# Real_Steel_Robotics.net
KiCad netlist of a schematic drawn in Altium Designer
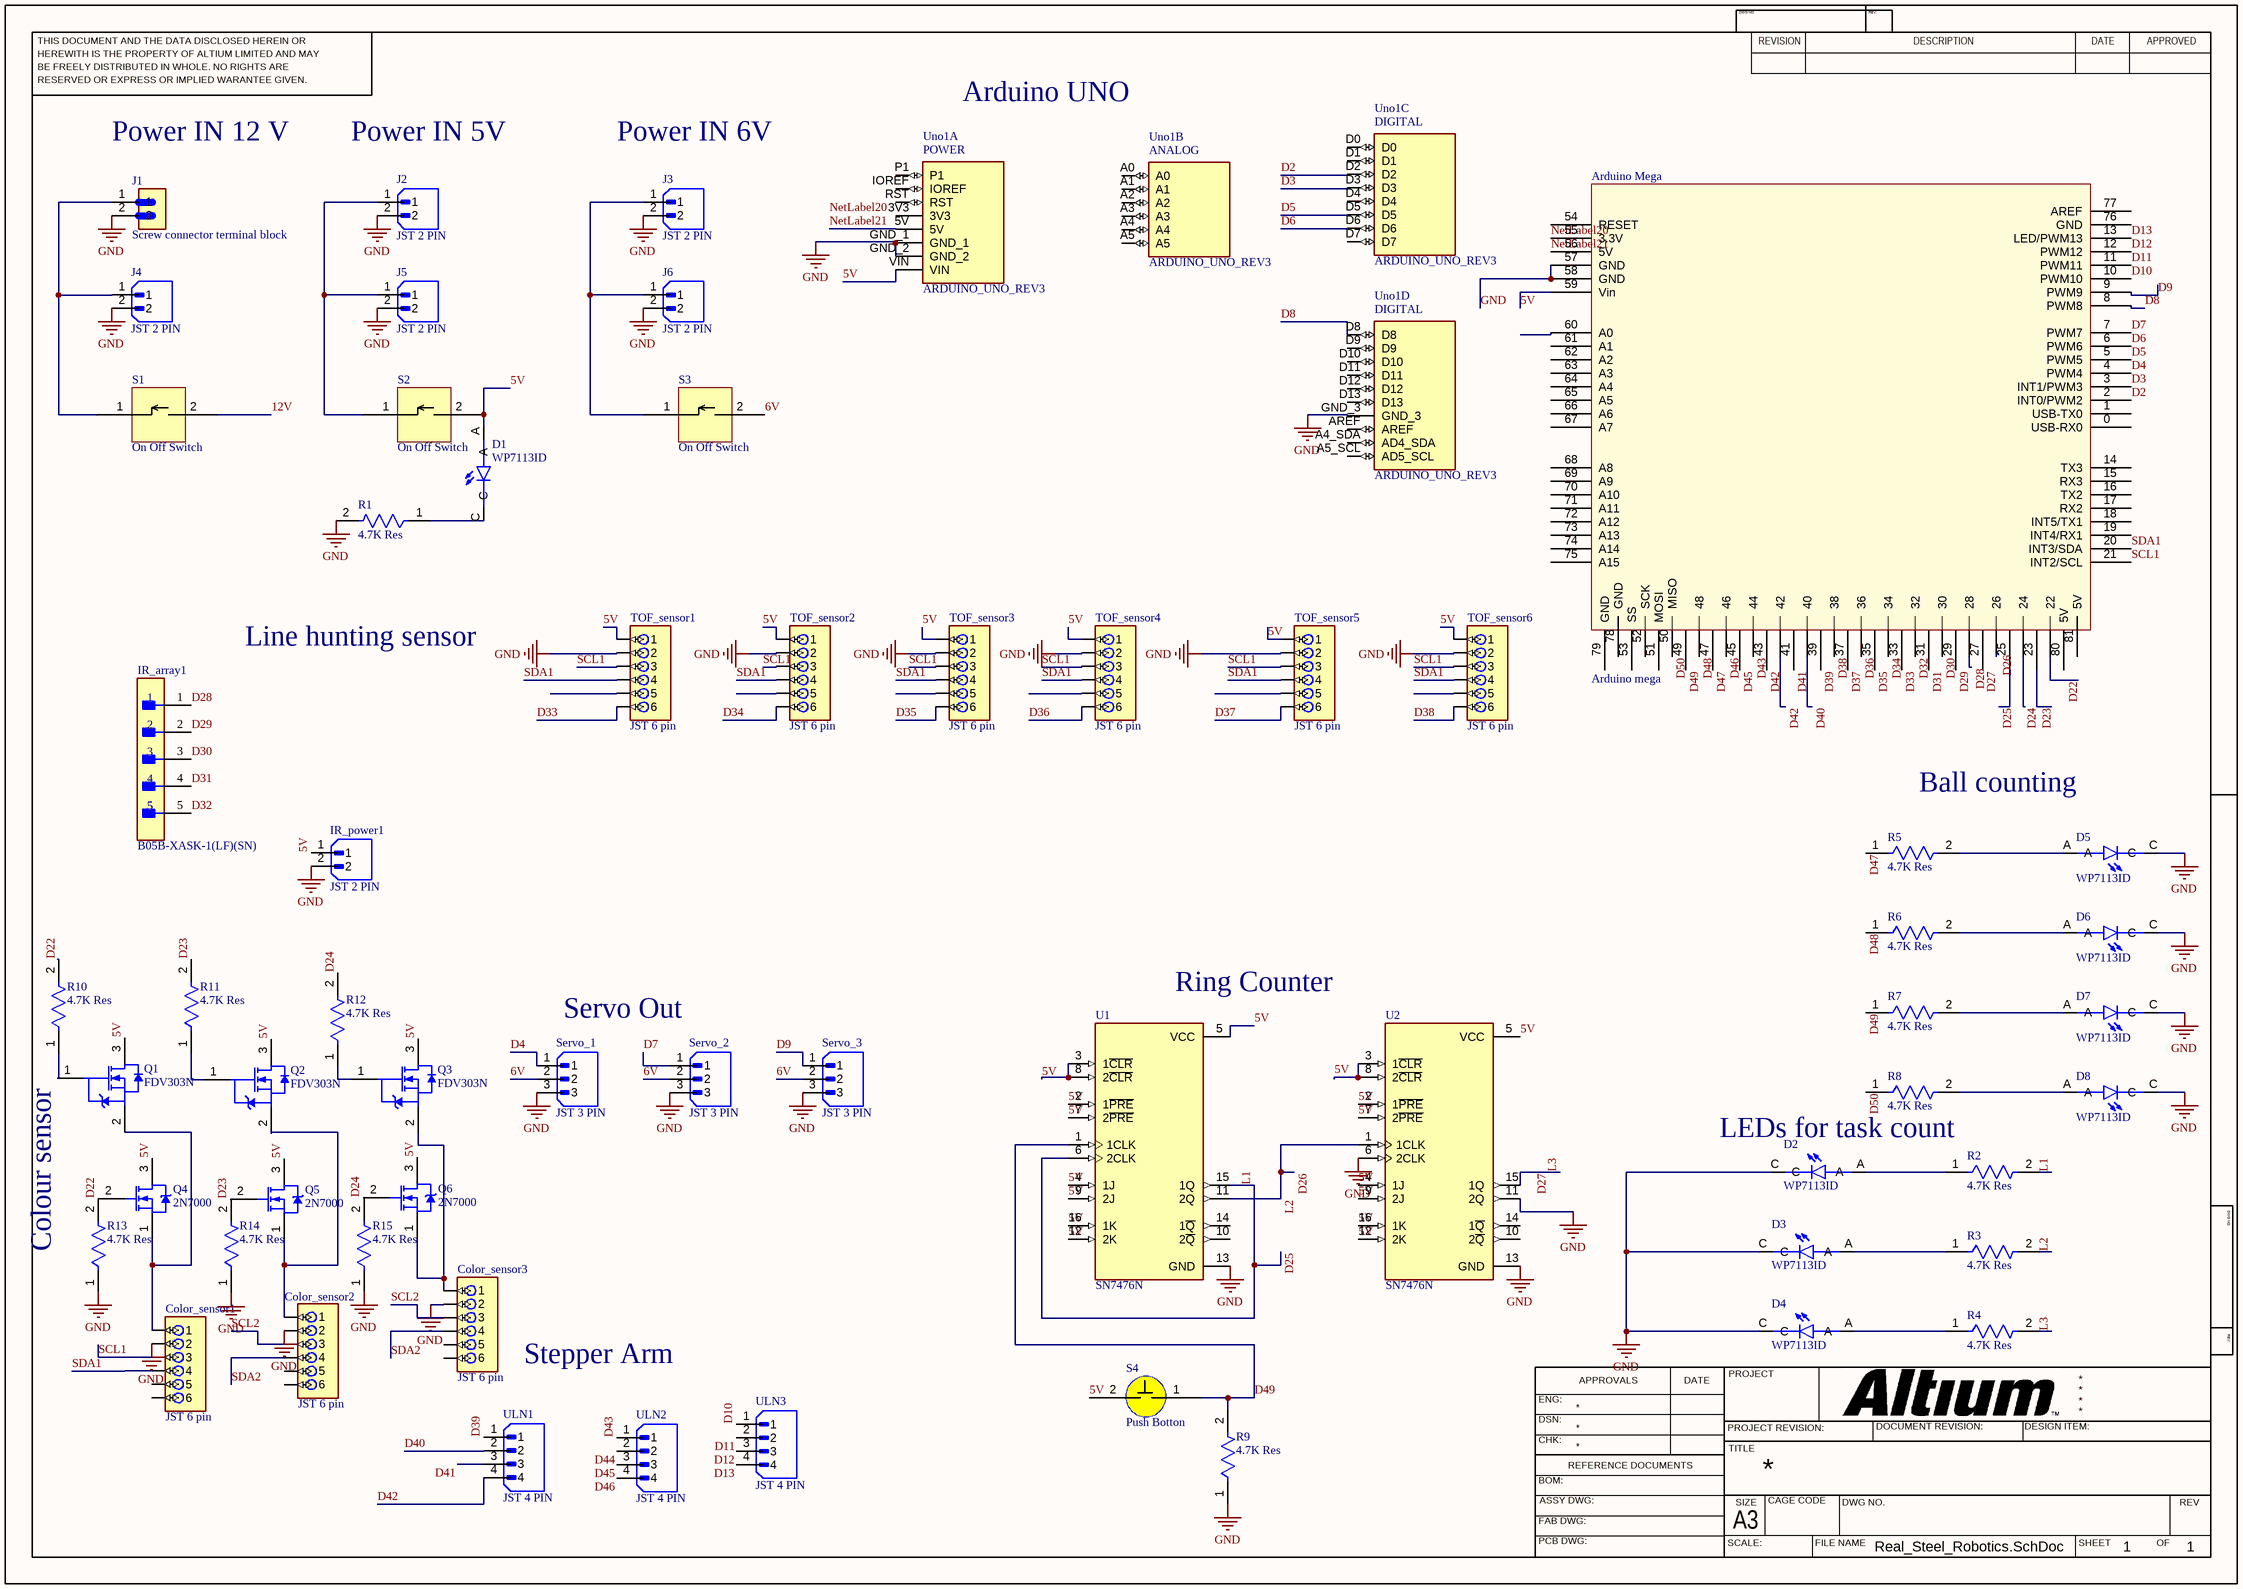
[diagram p0:  Real_Steel_Robotics.SchDoc]

(export (version "E")
  (design (tool "Eeschema 10.0.6"))
  (components
    (comp (ref "Arduino Mega")
      (value "Arduino mega")
      (footprint "Arduino mega")
      (libsource (lib "Real_Steel_Robotics") (part "Arduino mega"))
    )
    (comp (ref "Color_sensor1")
      (value "JST 6 pin")
      (footprint "JST 6 PIN")
      (description "Header B6B-ZR, 1.50mm, 6-contacts, top entry, THT, /2000/box")
      (fields (field (name "MANUFACTURER") "JST") (field (name "MANUFACTURER PART NUMBER") "B6B-ZR"))
      (libsource (lib "Real_Steel_Robotics") (part "JST 6 pin"))
    )
    (comp (ref "Color_sensor2")
      (value "JST 6 pin")
      (footprint "JST 6 PIN")
      (description "Header B6B-ZR, 1.50mm, 6-contacts, top entry, THT, /2000/box")
      (fields (field (name "MANUFACTURER") "JST") (field (name "MANUFACTURER PART NUMBER") "B6B-ZR"))
      (libsource (lib "Real_Steel_Robotics") (part "JST 6 pin"))
    )
    (comp (ref "Color_sensor3")
      (value "JST 6 pin")
      (footprint "JST 6 PIN")
      (description "Header B6B-ZR, 1.50mm, 6-contacts, top entry, THT, /2000/box")
      (fields (field (name "MANUFACTURER") "JST") (field (name "MANUFACTURER PART NUMBER") "B6B-ZR"))
      (libsource (lib "Real_Steel_Robotics") (part "JST 6 pin"))
    )
    (comp (ref "D1")
      (value "WP7113ID")
      (footprint "LED_WP7113ID")
      (description "Red 617nm LED Indication - Discrete 2V Radial")
      (fields (field (name "MF") "Kingbright"))
      (libsource (lib "Real_Steel_Robotics") (part "WP7113ID"))
    )
    (comp (ref "D2")
      (value "WP7113ID")
      (footprint "LED_WP7113ID")
      (description "Red 617nm LED Indication - Discrete 2V Radial")
      (fields (field (name "MF") "Kingbright"))
      (libsource (lib "Real_Steel_Robotics") (part "WP7113ID"))
    )
    (comp (ref "D3")
      (value "WP7113ID")
      (footprint "LED_WP7113ID")
      (description "Red 617nm LED Indication - Discrete 2V Radial")
      (fields (field (name "MF") "Kingbright"))
      (libsource (lib "Real_Steel_Robotics") (part "WP7113ID"))
    )
    (comp (ref "D4")
      (value "WP7113ID")
      (footprint "LED_WP7113ID")
      (description "Red 617nm LED Indication - Discrete 2V Radial")
      (fields (field (name "MF") "Kingbright"))
      (libsource (lib "Real_Steel_Robotics") (part "WP7113ID"))
    )
    (comp (ref "D5")
      (value "WP7113ID")
      (footprint "LED_WP7113ID")
      (description "Red 617nm LED Indication - Discrete 2V Radial")
      (fields (field (name "MF") "Kingbright"))
      (libsource (lib "Real_Steel_Robotics") (part "WP7113ID"))
    )
    (comp (ref "D6")
      (value "WP7113ID")
      (footprint "LED_WP7113ID")
      (description "Red 617nm LED Indication - Discrete 2V Radial")
      (fields (field (name "MF") "Kingbright"))
      (libsource (lib "Real_Steel_Robotics") (part "WP7113ID"))
    )
    (comp (ref "D7")
      (value "WP7113ID")
      (footprint "LED_WP7113ID")
      (description "Red 617nm LED Indication - Discrete 2V Radial")
      (fields (field (name "MF") "Kingbright"))
      (libsource (lib "Real_Steel_Robotics") (part "WP7113ID"))
    )
    (comp (ref "D8")
      (value "WP7113ID")
      (footprint "LED_WP7113ID")
      (description "Red 617nm LED Indication - Discrete 2V Radial")
      (fields (field (name "MF") "Kingbright"))
      (libsource (lib "Real_Steel_Robotics") (part "WP7113ID"))
    )
    (comp (ref "IR_array1")
      (value "B05B-XASK-1(LF)(SN)")
      (footprint "JST 5 PIN")
      (description "CONN HEADER VERT 5POS 2.5MM")
      (libsource (lib "Real_Steel_Robotics") (part "JST 5 PIN"))
    )
    (comp (ref "IR_power1")
      (value "JST 2 PIN")
      (footprint "JST 2 PIN")
      (description "Connector Header Through Hole 2 position 0.098 (2.50mm)")
      (fields (field (name "MF") "JST Sales") (field (name "MP") "B2B-XH-A (LF)(SN)"))
      (libsource (lib "Real_Steel_Robotics") (part "JST 2 PIN"))
    )
    (comp (ref "J1")
      (value "Screw connector terminal block")
      (footprint "Screw Connector")
      (libsource (lib "Real_Steel_Robotics") (part "Screw connector terminal block"))
    )
    (comp (ref "J2")
      (value "JST 2 PIN")
      (footprint "JST 2 PIN")
      (description "Connector Header Through Hole 2 position 0.098 (2.50mm)")
      (fields (field (name "MF") "JST Sales") (field (name "MP") "B2B-XH-A (LF)(SN)"))
      (libsource (lib "Real_Steel_Robotics") (part "JST 2 PIN"))
    )
    (comp (ref "J3")
      (value "JST 2 PIN")
      (footprint "JST 2 PIN")
      (description "Connector Header Through Hole 2 position 0.098 (2.50mm)")
      (fields (field (name "MF") "JST Sales") (field (name "MP") "B2B-XH-A (LF)(SN)"))
      (libsource (lib "Real_Steel_Robotics") (part "JST 2 PIN"))
    )
    (comp (ref "J4")
      (value "JST 2 PIN")
      (footprint "JST 2 PIN")
      (description "Connector Header Through Hole 2 position 0.098 (2.50mm)")
      (fields (field (name "MF") "JST Sales") (field (name "MP") "B2B-XH-A (LF)(SN)"))
      (libsource (lib "Real_Steel_Robotics") (part "JST 2 PIN"))
    )
    (comp (ref "J5")
      (value "JST 2 PIN")
      (footprint "JST 2 PIN")
      (description "Connector Header Through Hole 2 position 0.098 (2.50mm)")
      (fields (field (name "MF") "JST Sales") (field (name "MP") "B2B-XH-A (LF)(SN)"))
      (libsource (lib "Real_Steel_Robotics") (part "JST 2 PIN"))
    )
    (comp (ref "J6")
      (value "JST 2 PIN")
      (footprint "JST 2 PIN")
      (description "Connector Header Through Hole 2 position 0.098 (2.50mm)")
      (fields (field (name "MF") "JST Sales") (field (name "MP") "B2B-XH-A (LF)(SN)"))
      (libsource (lib "Real_Steel_Robotics") (part "JST 2 PIN"))
    )
    (comp (ref "Q1")
      (value "FDV303N")
      (footprint "FAIR-FDV303N-3_V")
      (fields (field (name "MANUFACTURER") "Fairchild"))
      (libsource (lib "Altium Content Vault") (part "NEMOS-GSD-3_D"))
    )
    (comp (ref "Q2")
      (value "FDV303N")
      (footprint "FAIR-FDV303N-3_V")
      (fields (field (name "MANUFACTURER") "Fairchild"))
      (libsource (lib "Altium Content Vault") (part "NEMOS-GSD-3_D"))
    )
    (comp (ref "Q3")
      (value "FDV303N")
      (footprint "FAIR-FDV303N-3_V")
      (fields (field (name "MANUFACTURER") "Fairchild"))
      (libsource (lib "Altium Content Vault") (part "NEMOS-GSD-3_D"))
    )
    (comp (ref "Q4")
      (value "2N7000")
      (footprint "ONSC-TO-92-3-29-11")
      (description "Small Signal MOSFET, 200 mA, 60 V, N-Channel, 3-Pin TO-92, Bulk Box")
      (fields (field (name "MANUFACTURER") "On Semiconductor"))
      (libsource (lib "Altium Content Vault") (part "ONSC-NMOS-S1G2D3-3"))
    )
    (comp (ref "Q5")
      (value "2N7000")
      (footprint "ONSC-TO-92-3-29-11")
      (description "Small Signal MOSFET, 200 mA, 60 V, N-Channel, 3-Pin TO-92, Bulk Box")
      (fields (field (name "MANUFACTURER") "On Semiconductor"))
      (libsource (lib "Altium Content Vault") (part "ONSC-NMOS-S1G2D3-3"))
    )
    (comp (ref "Q6")
      (value "2N7000")
      (footprint "ONSC-TO-92-3-29-11")
      (description "Small Signal MOSFET, 200 mA, 60 V, N-Channel, 3-Pin TO-92, Bulk Box")
      (fields (field (name "MANUFACTURER") "On Semiconductor"))
      (libsource (lib "Altium Content Vault") (part "ONSC-NMOS-S1G2D3-3"))
    )
    (comp (ref "R1")
      (value "4.7K Res")
      (footprint "4.7K res")
      (libsource (lib "Real_Steel_Robotics") (part "4.7K Res"))
    )
    (comp (ref "R2")
      (value "4.7K Res")
      (footprint "4.7K res")
      (libsource (lib "Real_Steel_Robotics") (part "4.7K Res"))
    )
    (comp (ref "R3")
      (value "4.7K Res")
      (footprint "4.7K res")
      (libsource (lib "Real_Steel_Robotics") (part "4.7K Res"))
    )
    (comp (ref "R4")
      (value "4.7K Res")
      (footprint "4.7K res")
      (libsource (lib "Real_Steel_Robotics") (part "4.7K Res"))
    )
    (comp (ref "R5")
      (value "4.7K Res")
      (footprint "4.7K res")
      (libsource (lib "Real_Steel_Robotics") (part "4.7K Res"))
    )
    (comp (ref "R6")
      (value "4.7K Res")
      (footprint "4.7K res")
      (libsource (lib "Real_Steel_Robotics") (part "4.7K Res"))
    )
    (comp (ref "R7")
      (value "4.7K Res")
      (footprint "4.7K res")
      (libsource (lib "Real_Steel_Robotics") (part "4.7K Res"))
    )
    (comp (ref "R8")
      (value "4.7K Res")
      (footprint "4.7K res")
      (libsource (lib "Real_Steel_Robotics") (part "4.7K Res"))
    )
    (comp (ref "R9")
      (value "4.7K Res")
      (footprint "4.7K res")
      (libsource (lib "Real_Steel_Robotics") (part "4.7K Res"))
    )
    (comp (ref "R10")
      (value "4.7K Res")
      (footprint "4.7K res")
      (libsource (lib "Real_Steel_Robotics") (part "4.7K Res"))
    )
    (comp (ref "R11")
      (value "4.7K Res")
      (footprint "4.7K res")
      (libsource (lib "Real_Steel_Robotics") (part "4.7K Res"))
    )
    (comp (ref "R12")
      (value "4.7K Res")
      (footprint "4.7K res")
      (libsource (lib "Real_Steel_Robotics") (part "4.7K Res"))
    )
    (comp (ref "R13")
      (value "4.7K Res")
      (footprint "4.7K res")
      (libsource (lib "Real_Steel_Robotics") (part "4.7K Res"))
    )
    (comp (ref "R14")
      (value "4.7K Res")
      (footprint "4.7K res")
      (libsource (lib "Real_Steel_Robotics") (part "4.7K Res"))
    )
    (comp (ref "R15")
      (value "4.7K Res")
      (footprint "4.7K res")
      (libsource (lib "Real_Steel_Robotics") (part "4.7K Res"))
    )
    (comp (ref "S1")
      (value "On Off Switch")
      (footprint "Switch")
      (libsource (lib "Real_Steel_Robotics") (part "On Off Switch"))
    )
    (comp (ref "S2")
      (value "On Off Switch")
      (footprint "Switch")
      (libsource (lib "Real_Steel_Robotics") (part "On Off Switch"))
    )
    (comp (ref "S3")
      (value "On Off Switch")
      (footprint "Switch")
      (libsource (lib "Real_Steel_Robotics") (part "On Off Switch"))
    )
    (comp (ref "S4")
      (value "Push Botton")
      (footprint "Push botton")
      (libsource (lib "Real_Steel_Robotics") (part "Push Botton"))
    )
    (comp (ref "Servo_1")
      (value "JST 3 PIN")
      (footprint "JST 3 PIN")
      (libsource (lib "Real_Steel_Robotics") (part "JST 3 PIN"))
    )
    (comp (ref "Servo_2")
      (value "JST 3 PIN")
      (footprint "JST 3 PIN")
      (libsource (lib "Real_Steel_Robotics") (part "JST 3 PIN"))
    )
    (comp (ref "Servo_3")
      (value "JST 3 PIN")
      (footprint "JST 3 PIN")
      (libsource (lib "Real_Steel_Robotics") (part "JST 3 PIN"))
    )
    (comp (ref "TOF_sensor1")
      (value "JST 6 pin")
      (footprint "JST 6 PIN")
      (description "Header B6B-ZR, 1.50mm, 6-contacts, top entry, THT, /2000/box")
      (fields (field (name "MANUFACTURER") "JST") (field (name "MANUFACTURER PART NUMBER") "B6B-ZR"))
      (libsource (lib "Real_Steel_Robotics") (part "JST 6 pin"))
    )
    (comp (ref "TOF_sensor2")
      (value "JST 6 pin")
      (footprint "JST 6 PIN")
      (description "Header B6B-ZR, 1.50mm, 6-contacts, top entry, THT, /2000/box")
      (fields (field (name "MANUFACTURER") "JST") (field (name "MANUFACTURER PART NUMBER") "B6B-ZR"))
      (libsource (lib "Real_Steel_Robotics") (part "JST 6 pin"))
    )
    (comp (ref "TOF_sensor3")
      (value "JST 6 pin")
      (footprint "JST 6 PIN")
      (description "Header B6B-ZR, 1.50mm, 6-contacts, top entry, THT, /2000/box")
      (fields (field (name "MANUFACTURER") "JST") (field (name "MANUFACTURER PART NUMBER") "B6B-ZR"))
      (libsource (lib "Real_Steel_Robotics") (part "JST 6 pin"))
    )
    (comp (ref "TOF_sensor4")
      (value "JST 6 pin")
      (footprint "JST 6 PIN")
      (description "Header B6B-ZR, 1.50mm, 6-contacts, top entry, THT, /2000/box")
      (fields (field (name "MANUFACTURER") "JST") (field (name "MANUFACTURER PART NUMBER") "B6B-ZR"))
      (libsource (lib "Real_Steel_Robotics") (part "JST 6 pin"))
    )
    (comp (ref "TOF_sensor5")
      (value "JST 6 pin")
      (footprint "JST 6 PIN")
      (description "Header B6B-ZR, 1.50mm, 6-contacts, top entry, THT, /2000/box")
      (fields (field (name "MANUFACTURER") "JST") (field (name "MANUFACTURER PART NUMBER") "B6B-ZR"))
      (libsource (lib "Real_Steel_Robotics") (part "JST 6 pin"))
    )
    (comp (ref "TOF_sensor6")
      (value "JST 6 pin")
      (footprint "JST 6 PIN")
      (description "Header B6B-ZR, 1.50mm, 6-contacts, top entry, THT, /2000/box")
      (fields (field (name "MANUFACTURER") "JST") (field (name "MANUFACTURER PART NUMBER") "B6B-ZR"))
      (libsource (lib "Real_Steel_Robotics") (part "JST 6 pin"))
    )
    (comp (ref "U1")
      (value "SN7476N")
      (footprint "SN7476 IC")
      (description "Flip Flops Dual J-K Positive-Edge-Triggered Flip-Flops with Preset and Clear 16-PDIP 0 to 70")
      (fields (field (name "MF") "Texas Instruments"))
      (libsource (lib "Real_Steel_Robotics") (part "SN7476N"))
    )
    (comp (ref "U2")
      (value "SN7476N")
      (footprint "SN7476 IC")
      (description "Flip Flops Dual J-K Positive-Edge-Triggered Flip-Flops with Preset and Clear 16-PDIP 0 to 70")
      (fields (field (name "MF") "Texas Instruments"))
      (libsource (lib "Real_Steel_Robotics") (part "SN7476N"))
    )
    (comp (ref "ULN1")
      (value "JST 4 PIN")
      (footprint "JST 4 PIN")
      (libsource (lib "Real_Steel_Robotics") (part "JST 4 PIN"))
    )
    (comp (ref "ULN2")
      (value "JST 4 PIN")
      (footprint "JST 4 PIN")
      (libsource (lib "Real_Steel_Robotics") (part "JST 4 PIN"))
    )
    (comp (ref "ULN3")
      (value "JST 4 PIN")
      (footprint "JST 4 PIN")
      (libsource (lib "Real_Steel_Robotics") (part "JST 4 PIN"))
    )
    (comp (ref "Uno1")
      (value "ARDUINO_UNO_REV3")
      (footprint "ARDUINO_ARDUINO_UNO_REV3")
      (description "Microcontroller board based on the ATmega328P.")
      (fields (field (name "MF") "Arduino") (field (name "MP") "ARDUINO UNO REV3"))
      (libsource (lib "Real_Steel_Robotics") (part "ARDUINO_UNO_REV3"))
    )
  )
  (nets
    (net (code "1") (name "/5V") (class "Default")
      (node (ref "Arduino Mega") (pin "59") (pinfunction "Vin_59") (pintype "passive"))
      (node (ref "D1") (pin "A") (pinfunction "A_A") (pintype "passive"))
      (node (ref "IR_power1") (pin "1") (pinfunction "1_1") (pintype "passive"))
      (node (ref "Q1") (pin "3") (pinfunction "D_3") (pintype "passive"))
      (node (ref "Q2") (pin "3") (pinfunction "D_3") (pintype "passive"))
      (node (ref "Q3") (pin "3") (pinfunction "D_3") (pintype "passive"))
      (node (ref "Q4") (pin "3") (pinfunction "D_3") (pintype "passive"))
      (node (ref "Q5") (pin "3") (pinfunction "D_3") (pintype "passive"))
      (node (ref "Q6") (pin "3") (pinfunction "D_3") (pintype "passive"))
      (node (ref "S2") (pin "2") (pintype "passive"))
      (node (ref "S4") (pin "2") (pinfunction "P29_2") (pintype "passive"))
      (node (ref "TOF_sensor1") (pin "1") (pinfunction "1_1") (pintype "bidirectional"))
      (node (ref "TOF_sensor2") (pin "1") (pinfunction "1_1") (pintype "bidirectional"))
      (node (ref "TOF_sensor3") (pin "1") (pinfunction "1_1") (pintype "bidirectional"))
      (node (ref "TOF_sensor4") (pin "1") (pinfunction "1_1") (pintype "bidirectional"))
      (node (ref "TOF_sensor5") (pin "1") (pinfunction "1_1") (pintype "bidirectional"))
      (node (ref "TOF_sensor6") (pin "1") (pinfunction "1_1") (pintype "bidirectional"))
      (node (ref "U1") (pin "12") (pinfunction "2K_12") (pintype "input"))
      (node (ref "U1") (pin "16") (pinfunction "1K_16") (pintype "input"))
      (node (ref "U1") (pin "2") (pinfunction "1~{PRE}_2") (pintype "input"))
      (node (ref "U1") (pin "3") (pinfunction "1~{CLR}_3") (pintype "input"))
      (node (ref "U1") (pin "4") (pinfunction "1J_4") (pintype "input"))
      (node (ref "U1") (pin "5") (pinfunction "VCC_5") (pintype "power_in"))
      (node (ref "U1") (pin "7") (pinfunction "2~{PRE}_7") (pintype "input"))
      (node (ref "U1") (pin "8") (pinfunction "2~{CLR}_8") (pintype "input"))
      (node (ref "U1") (pin "9") (pinfunction "2J_9") (pintype "input"))
      (node (ref "U2") (pin "12") (pinfunction "2K_12") (pintype "input"))
      (node (ref "U2") (pin "16") (pinfunction "1K_16") (pintype "input"))
      (node (ref "U2") (pin "2") (pinfunction "1~{PRE}_2") (pintype "input"))
      (node (ref "U2") (pin "3") (pinfunction "1~{CLR}_3") (pintype "input"))
      (node (ref "U2") (pin "4") (pinfunction "1J_4") (pintype "input"))
      (node (ref "U2") (pin "5") (pinfunction "VCC_5") (pintype "power_in"))
      (node (ref "U2") (pin "7") (pinfunction "2~{PRE}_7") (pintype "input"))
      (node (ref "U2") (pin "8") (pinfunction "2~{CLR}_8") (pintype "input"))
      (node (ref "U2") (pin "9") (pinfunction "2J_9") (pintype "input"))
      (node (ref "Uno1") (pin "VIN") (pinfunction "VIN_VIN") (pintype "power_in"))
    )
    (net (code "2") (name "/6V") (class "Default")
      (node (ref "S3") (pin "2") (pintype "passive"))
      (node (ref "Servo_1") (pin "2") (pinfunction "2_2") (pintype "passive"))
      (node (ref "Servo_2") (pin "2") (pinfunction "2_2") (pintype "passive"))
      (node (ref "Servo_3") (pin "2") (pinfunction "2_2") (pintype "passive"))
    )
    (net (code "3") (name "/12V") (class "Default") (node (ref "S1") (pin "2") (pintype "passive")))
    (net (code "4") (name "/D2") (class "Default")
      (node (ref "Arduino Mega") (pin "2") (pinfunction "INT0/PWM2_2") (pintype "passive"))
      (node (ref "Uno1") (pin "D2") (pinfunction "D2_D2") (pintype "bidirectional"))
    )
    (net (code "5") (name "/D3") (class "Default")
      (node (ref "Arduino Mega") (pin "3") (pinfunction "INT1/PWM3_3") (pintype "passive"))
      (node (ref "Uno1") (pin "D3") (pinfunction "D3_D3") (pintype "bidirectional"))
    )
    (net (code "6") (name "/D4") (class "Default")
      (node (ref "Arduino Mega") (pin "4") (pinfunction "PWM4_4") (pintype "passive"))
      (node (ref "Servo_1") (pin "1") (pinfunction "1_1") (pintype "passive"))
    )
    (net (code "7") (name "/D5") (class "Default")
      (node (ref "Arduino Mega") (pin "5") (pinfunction "PWM5_5") (pintype "passive"))
      (node (ref "Uno1") (pin "D5") (pinfunction "D5_D5") (pintype "bidirectional"))
    )
    (net (code "8") (name "/D6") (class "Default")
      (node (ref "Arduino Mega") (pin "6") (pinfunction "PWM6_6") (pintype "passive"))
      (node (ref "Uno1") (pin "D6") (pinfunction "D6_D6") (pintype "bidirectional"))
    )
    (net (code "9") (name "/D7") (class "Default")
      (node (ref "Arduino Mega") (pin "7") (pinfunction "PWM7_7") (pintype "passive"))
      (node (ref "Servo_2") (pin "1") (pinfunction "1_1") (pintype "passive"))
    )
    (net (code "10") (name "/D8") (class "Default")
      (node (ref "Arduino Mega") (pin "8") (pinfunction "PWM8_8") (pintype "passive"))
      (node (ref "Uno1") (pin "D8") (pinfunction "D8_D8") (pintype "bidirectional"))
    )
    (net (code "11") (name "/D9") (class "Default")
      (node (ref "Arduino Mega") (pin "9") (pinfunction "PWM9_9") (pintype "passive"))
      (node (ref "Servo_3") (pin "1") (pinfunction "1_1") (pintype "passive"))
    )
    (net (code "12") (name "/D10") (class "Default")
      (node (ref "Arduino Mega") (pin "10") (pinfunction "PWM10_10") (pintype "passive"))
      (node (ref "ULN3") (pin "1") (pinfunction "1_1") (pintype "passive"))
    )
    (net (code "13") (name "/D11") (class "Default")
      (node (ref "Arduino Mega") (pin "11") (pinfunction "PWM11_11") (pintype "passive"))
      (node (ref "ULN3") (pin "2") (pinfunction "2_2") (pintype "passive"))
    )
    (net (code "14") (name "/D12") (class "Default")
      (node (ref "Arduino Mega") (pin "12") (pinfunction "PWM12_12") (pintype "passive"))
      (node (ref "ULN3") (pin "3") (pinfunction "3_3") (pintype "passive"))
    )
    (net (code "15") (name "/D13") (class "Default")
      (node (ref "Arduino Mega") (pin "13") (pinfunction "LED/PWM13_13") (pintype "passive"))
      (node (ref "ULN3") (pin "4") (pinfunction "4_4") (pintype "passive"))
    )
    (net (code "16") (name "/D22") (class "Default")
      (node (ref "Arduino Mega") (pin "22") (pinfunction "22_22") (pintype "passive"))
      (node (ref "Q4") (pin "2") (pinfunction "G_2") (pintype "passive"))
      (node (ref "R10") (pin "2") (pinfunction "2_2") (pintype "passive"))
      (node (ref "R13") (pin "2") (pinfunction "2_2") (pintype "passive"))
    )
    (net (code "17") (name "/D23") (class "Default")
      (node (ref "Arduino Mega") (pin "23") (pinfunction "23_23") (pintype "passive"))
      (node (ref "Q5") (pin "2") (pinfunction "G_2") (pintype "passive"))
      (node (ref "R11") (pin "2") (pinfunction "2_2") (pintype "passive"))
    )
    (net (code "18") (name "/D24") (class "Default")
      (node (ref "Arduino Mega") (pin "24") (pinfunction "24_24") (pintype "passive"))
      (node (ref "Q6") (pin "2") (pinfunction "G_2") (pintype "passive"))
      (node (ref "R12") (pin "2") (pinfunction "2_2") (pintype "passive"))
    )
    (net (code "19") (name "/D25") (class "Default")
      (node (ref "Arduino Mega") (pin "25") (pinfunction "25_25") (pintype "passive"))
      (node (ref "R2") (pin "2") (pinfunction "2_2") (pintype "passive"))
      (node (ref "U1") (pin "15") (pinfunction "1Q_15") (pintype "output"))
      (node (ref "U1") (pin "6") (pinfunction "2CLK_6") (pintype "input"))
    )
    (net (code "20") (name "/D26") (class "Default")
      (node (ref "Arduino Mega") (pin "26") (pinfunction "26_26") (pintype "passive"))
      (node (ref "R3") (pin "2") (pinfunction "2_2") (pintype "passive"))
      (node (ref "U1") (pin "11") (pinfunction "2Q_11") (pintype "output"))
      (node (ref "U2") (pin "1") (pinfunction "1CLK_1") (pintype "input"))
    )
    (net (code "21") (name "/D27") (class "Default")
      (node (ref "Arduino Mega") (pin "27") (pinfunction "27_27") (pintype "passive"))
      (node (ref "R4") (pin "2") (pinfunction "2_2") (pintype "passive"))
      (node (ref "U2") (pin "15") (pinfunction "1Q_15") (pintype "output"))
    )
    (net (code "22") (name "/D28") (class "Default")
      (node (ref "Arduino Mega") (pin "28") (pinfunction "28_28") (pintype "passive"))
      (node (ref "IR_array1") (pin "1") (pinfunction "1_1") (pintype "passive"))
    )
    (net (code "23") (name "/D29") (class "Default")
      (node (ref "Arduino Mega") (pin "29") (pinfunction "29_29") (pintype "passive"))
      (node (ref "IR_array1") (pin "2") (pinfunction "2_2") (pintype "passive"))
    )
    (net (code "24") (name "/D30") (class "Default")
      (node (ref "Arduino Mega") (pin "30") (pinfunction "30_30") (pintype "passive"))
      (node (ref "IR_array1") (pin "3") (pinfunction "3_3") (pintype "passive"))
    )
    (net (code "25") (name "/D31") (class "Default")
      (node (ref "Arduino Mega") (pin "31") (pinfunction "31_31") (pintype "passive"))
      (node (ref "IR_array1") (pin "4") (pinfunction "4_4") (pintype "passive"))
    )
    (net (code "26") (name "/D32") (class "Default")
      (node (ref "Arduino Mega") (pin "32") (pinfunction "32_32") (pintype "passive"))
      (node (ref "IR_array1") (pin "5") (pinfunction "5_5") (pintype "passive"))
    )
    (net (code "27") (name "/D33") (class "Default")
      (node (ref "Arduino Mega") (pin "33") (pinfunction "33_33") (pintype "passive"))
      (node (ref "TOF_sensor1") (pin "6") (pinfunction "6_6") (pintype "bidirectional"))
    )
    (net (code "28") (name "/D34") (class "Default")
      (node (ref "Arduino Mega") (pin "34") (pinfunction "34_34") (pintype "passive"))
      (node (ref "TOF_sensor2") (pin "6") (pinfunction "6_6") (pintype "bidirectional"))
    )
    (net (code "29") (name "/D35") (class "Default")
      (node (ref "Arduino Mega") (pin "35") (pinfunction "35_35") (pintype "passive"))
      (node (ref "TOF_sensor3") (pin "6") (pinfunction "6_6") (pintype "bidirectional"))
    )
    (net (code "30") (name "/D36") (class "Default")
      (node (ref "Arduino Mega") (pin "36") (pinfunction "36_36") (pintype "passive"))
      (node (ref "TOF_sensor4") (pin "6") (pinfunction "6_6") (pintype "bidirectional"))
    )
    (net (code "31") (name "/D37") (class "Default")
      (node (ref "Arduino Mega") (pin "37") (pinfunction "37_37") (pintype "passive"))
      (node (ref "TOF_sensor5") (pin "6") (pinfunction "6_6") (pintype "bidirectional"))
    )
    (net (code "32") (name "/D38") (class "Default")
      (node (ref "Arduino Mega") (pin "38") (pinfunction "38_38") (pintype "passive"))
      (node (ref "TOF_sensor6") (pin "6") (pinfunction "6_6") (pintype "bidirectional"))
    )
    (net (code "33") (name "/D39") (class "Default")
      (node (ref "Arduino Mega") (pin "39") (pinfunction "39_39") (pintype "passive"))
      (node (ref "ULN1") (pin "1") (pinfunction "1_1") (pintype "passive"))
    )
    (net (code "34") (name "/D40") (class "Default")
      (node (ref "Arduino Mega") (pin "40") (pinfunction "40_40") (pintype "passive"))
      (node (ref "ULN1") (pin "2") (pinfunction "2_2") (pintype "passive"))
    )
    (net (code "35") (name "/D41") (class "Default")
      (node (ref "Arduino Mega") (pin "41") (pinfunction "41_41") (pintype "passive"))
      (node (ref "ULN1") (pin "3") (pinfunction "3_3") (pintype "passive"))
    )
    (net (code "36") (name "/D42") (class "Default")
      (node (ref "Arduino Mega") (pin "42") (pinfunction "42_42") (pintype "passive"))
      (node (ref "Arduino Mega") (pin "43") (pinfunction "43_43") (pintype "passive"))
      (node (ref "ULN1") (pin "4") (pinfunction "4_4") (pintype "passive"))
    )
    (net (code "37") (name "/D43") (class "Default")
      (node (ref "Arduino Mega") (pin "44") (pinfunction "44_44") (pintype "passive"))
      (node (ref "ULN2") (pin "1") (pinfunction "1_1") (pintype "passive"))
    )
    (net (code "38") (name "/D44") (class "Default")
      (node (ref "ULN2") (pin "2") (pinfunction "2_2") (pintype "passive"))
    )
    (net (code "39") (name "/D45") (class "Default")
      (node (ref "Arduino Mega") (pin "45") (pinfunction "45_45") (pintype "passive"))
      (node (ref "ULN2") (pin "3") (pinfunction "3_3") (pintype "passive"))
    )
    (net (code "40") (name "/D46") (class "Default")
      (node (ref "Arduino Mega") (pin "46") (pinfunction "46_46") (pintype "passive"))
      (node (ref "ULN2") (pin "4") (pinfunction "4_4") (pintype "passive"))
    )
    (net (code "41") (name "/D47") (class "Default")
      (node (ref "Arduino Mega") (pin "47") (pinfunction "47_47") (pintype "passive"))
      (node (ref "R5") (pin "1") (pinfunction "1_1") (pintype "passive"))
    )
    (net (code "42") (name "/D48") (class "Default")
      (node (ref "Arduino Mega") (pin "48") (pinfunction "48_48") (pintype "passive"))
      (node (ref "R6") (pin "1") (pinfunction "1_1") (pintype "passive"))
    )
    (net (code "43") (name "/D49") (class "Default")
      (node (ref "Arduino Mega") (pin "49") (pinfunction "49_49") (pintype "passive"))
      (node (ref "R7") (pin "1") (pinfunction "1_1") (pintype "passive"))
      (node (ref "R9") (pin "2") (pinfunction "2_2") (pintype "passive"))
      (node (ref "S4") (pin "1") (pinfunction "P30_1") (pintype "passive"))
      (node (ref "U1") (pin "1") (pinfunction "1CLK_1") (pintype "input"))
    )
    (net (code "44") (name "/D50") (class "Default")
      (node (ref "Arduino Mega") (pin "50") (pinfunction "MISO_50") (pintype "passive"))
      (node (ref "R8") (pin "1") (pinfunction "1_1") (pintype "passive"))
    )
    (net (code "45") (name "/NetLabel20") (class "Default")
      (node (ref "Arduino Mega") (pin "55") (pinfunction "3.3V_55") (pintype "passive"))
    )
    (net (code "46") (name "/NetLabel21") (class "Default")
      (node (ref "Arduino Mega") (pin "56") (pinfunction "5V_56") (pintype "passive"))
      (node (ref "Uno1") (pin "5V") (pinfunction "5V_5V") (pintype "power_in"))
    )
    (net (code "47") (name "/SCL1") (class "Default")
      (node (ref "Arduino Mega") (pin "21") (pinfunction "INT2/SCL_21") (pintype "passive"))
      (node (ref "Color_sensor1") (pin "3") (pinfunction "3_3") (pintype "bidirectional"))
      (node (ref "TOF_sensor1") (pin "3") (pinfunction "3_3") (pintype "bidirectional"))
      (node (ref "TOF_sensor2") (pin "3") (pinfunction "3_3") (pintype "bidirectional"))
      (node (ref "TOF_sensor3") (pin "3") (pinfunction "3_3") (pintype "bidirectional"))
      (node (ref "TOF_sensor4") (pin "3") (pinfunction "3_3") (pintype "bidirectional"))
      (node (ref "TOF_sensor5") (pin "3") (pinfunction "3_3") (pintype "bidirectional"))
      (node (ref "TOF_sensor6") (pin "3") (pinfunction "3_3") (pintype "bidirectional"))
    )
    (net (code "48") (name "/SCL2") (class "Default")
      (node (ref "Color_sensor2") (pin "3") (pinfunction "3_3") (pintype "bidirectional"))
      (node (ref "Color_sensor3") (pin "3") (pinfunction "3_3") (pintype "bidirectional"))
    )
    (net (code "49") (name "/SDA1") (class "Default")
      (node (ref "Arduino Mega") (pin "20") (pinfunction "INT3/SDA_20") (pintype "passive"))
      (node (ref "Color_sensor1") (pin "4") (pinfunction "4_4") (pintype "bidirectional"))
      (node (ref "TOF_sensor1") (pin "4") (pinfunction "4_4") (pintype "bidirectional"))
      (node (ref "TOF_sensor2") (pin "4") (pinfunction "4_4") (pintype "bidirectional"))
      (node (ref "TOF_sensor3") (pin "4") (pinfunction "4_4") (pintype "bidirectional"))
      (node (ref "TOF_sensor4") (pin "4") (pinfunction "4_4") (pintype "bidirectional"))
      (node (ref "TOF_sensor5") (pin "4") (pinfunction "4_4") (pintype "bidirectional"))
      (node (ref "TOF_sensor6") (pin "4") (pinfunction "4_4") (pintype "bidirectional"))
    )
    (net (code "50") (name "/SDA2") (class "Default")
      (node (ref "Color_sensor2") (pin "4") (pinfunction "4_4") (pintype "bidirectional"))
      (node (ref "Color_sensor3") (pin "4") (pinfunction "4_4") (pintype "bidirectional"))
    )
    (net (code "51") (name "GND") (class "Default")
      (node (ref "Arduino Mega") (pin "57") (pinfunction "GND_57") (pintype "passive"))
      (node (ref "Arduino Mega") (pin "58") (pinfunction "GND_58") (pintype "passive"))
      (node (ref "Color_sensor1") (pin "2") (pinfunction "2_2") (pintype "bidirectional"))
      (node (ref "Color_sensor2") (pin "2") (pinfunction "2_2") (pintype "bidirectional"))
      (node (ref "Color_sensor3") (pin "2") (pinfunction "2_2") (pintype "bidirectional"))
      (node (ref "D2") (pin "C") (pinfunction "C_C") (pintype "passive"))
      (node (ref "D3") (pin "C") (pinfunction "C_C") (pintype "passive"))
      (node (ref "D4") (pin "C") (pinfunction "C_C") (pintype "passive"))
      (node (ref "D5") (pin "C") (pinfunction "C_C") (pintype "passive"))
      (node (ref "D6") (pin "C") (pinfunction "C_C") (pintype "passive"))
      (node (ref "D7") (pin "C") (pinfunction "C_C") (pintype "passive"))
      (node (ref "D8") (pin "C") (pinfunction "C_C") (pintype "passive"))
      (node (ref "IR_power1") (pin "2") (pinfunction "2_2") (pintype "passive"))
      (node (ref "J1") (pin "2") (pinfunction "2_2") (pintype "passive"))
      (node (ref "J2") (pin "2") (pinfunction "2_2") (pintype "passive"))
      (node (ref "J3") (pin "2") (pinfunction "2_2") (pintype "passive"))
      (node (ref "J4") (pin "2") (pinfunction "2_2") (pintype "passive"))
      (node (ref "J5") (pin "2") (pinfunction "2_2") (pintype "passive"))
      (node (ref "J6") (pin "2") (pinfunction "2_2") (pintype "passive"))
      (node (ref "R1") (pin "2") (pinfunction "2_2") (pintype "passive"))
      (node (ref "R14") (pin "1") (pinfunction "1_1") (pintype "passive"))
      (node (ref "R9") (pin "1") (pinfunction "1_1") (pintype "passive"))
      (node (ref "Servo_1") (pin "3") (pinfunction "3_3") (pintype "passive"))
      (node (ref "Servo_2") (pin "3") (pinfunction "3_3") (pintype "passive"))
      (node (ref "Servo_3") (pin "3") (pinfunction "3_3") (pintype "passive"))
      (node (ref "TOF_sensor1") (pin "2") (pinfunction "2_2") (pintype "bidirectional"))
      (node (ref "TOF_sensor2") (pin "2") (pinfunction "2_2") (pintype "bidirectional"))
      (node (ref "TOF_sensor3") (pin "2") (pinfunction "2_2") (pintype "bidirectional"))
      (node (ref "TOF_sensor4") (pin "2") (pinfunction "2_2") (pintype "bidirectional"))
      (node (ref "TOF_sensor5") (pin "2") (pinfunction "2_2") (pintype "bidirectional"))
      (node (ref "TOF_sensor6") (pin "2") (pinfunction "2_2") (pintype "bidirectional"))
      (node (ref "U1") (pin "13") (pinfunction "GND_13") (pintype "power_in"))
      (node (ref "U2") (pin "11") (pinfunction "2Q_11") (pintype "output"))
      (node (ref "U2") (pin "13") (pinfunction "GND_13") (pintype "power_in"))
      (node (ref "U2") (pin "6") (pinfunction "2CLK_6") (pintype "input"))
      (node (ref "Uno1") (pin "GND_1") (pinfunction "GND_1_GND_1") (pintype "power_in"))
      (node (ref "Uno1") (pin "GND_2") (pinfunction "GND_2_GND_2") (pintype "power_in"))
      (node (ref "Uno1") (pin "GND_3") (pinfunction "GND_3_GND_3") (pintype "power_in"))
    )
    (net (code "52") (name "Net-(D1-PadC)") (class "Default")
      (node (ref "D1") (pin "C") (pinfunction "C_C") (pintype "passive"))
      (node (ref "R1") (pin "1") (pinfunction "1_1") (pintype "passive"))
    )
    (net (code "53") (name "Net-(D2-PadA)") (class "Default")
      (node (ref "D2") (pin "A") (pinfunction "A_A") (pintype "passive"))
      (node (ref "R2") (pin "1") (pinfunction "1_1") (pintype "passive"))
    )
    (net (code "54") (name "Net-(D3-PadA)") (class "Default")
      (node (ref "D3") (pin "A") (pinfunction "A_A") (pintype "passive"))
      (node (ref "R3") (pin "1") (pinfunction "1_1") (pintype "passive"))
    )
    (net (code "55") (name "Net-(D4-PadA)") (class "Default")
      (node (ref "D4") (pin "A") (pinfunction "A_A") (pintype "passive"))
      (node (ref "R4") (pin "1") (pinfunction "1_1") (pintype "passive"))
    )
    (net (code "56") (name "Net-(D5-PadA)") (class "Default")
      (node (ref "D5") (pin "A") (pinfunction "A_A") (pintype "passive"))
      (node (ref "R5") (pin "2") (pinfunction "2_2") (pintype "passive"))
    )
    (net (code "57") (name "Net-(D6-PadA)") (class "Default")
      (node (ref "D6") (pin "A") (pinfunction "A_A") (pintype "passive"))
      (node (ref "R6") (pin "2") (pinfunction "2_2") (pintype "passive"))
    )
    (net (code "58") (name "Net-(D7-PadA)") (class "Default")
      (node (ref "D7") (pin "A") (pinfunction "A_A") (pintype "passive"))
      (node (ref "R7") (pin "2") (pinfunction "2_2") (pintype "passive"))
    )
    (net (code "59") (name "Net-(D8-PadA)") (class "Default")
      (node (ref "D8") (pin "A") (pinfunction "A_A") (pintype "passive"))
      (node (ref "R8") (pin "2") (pinfunction "2_2") (pintype "passive"))
    )
    (net (code "60") (name "Net-(Q1-G)") (class "Default")
      (node (ref "Q1") (pin "1") (pinfunction "G_1") (pintype "passive"))
      (node (ref "R10") (pin "1") (pinfunction "1_1") (pintype "passive"))
    )
    (net (code "61") (name "Net-(Q1-S)") (class "Default")
      (node (ref "Color_sensor1") (pin "1") (pinfunction "1_1") (pintype "bidirectional"))
      (node (ref "Q1") (pin "2") (pinfunction "S_2") (pintype "passive"))
      (node (ref "Q4") (pin "1") (pinfunction "S_1") (pintype "passive"))
    )
    (net (code "62") (name "Net-(Q2-G)") (class "Default")
      (node (ref "Q2") (pin "1") (pinfunction "G_1") (pintype "passive"))
      (node (ref "R11") (pin "1") (pinfunction "1_1") (pintype "passive"))
    )
    (net (code "63") (name "Net-(Q2-S)") (class "Default")
      (node (ref "Color_sensor2") (pin "1") (pinfunction "1_1") (pintype "bidirectional"))
      (node (ref "Q2") (pin "2") (pinfunction "S_2") (pintype "passive"))
      (node (ref "Q5") (pin "1") (pinfunction "S_1") (pintype "passive"))
    )
    (net (code "64") (name "Net-(Q3-G)") (class "Default")
      (node (ref "Q3") (pin "1") (pinfunction "G_1") (pintype "passive"))
      (node (ref "R12") (pin "1") (pinfunction "1_1") (pintype "passive"))
    )
    (net (code "65") (name "Net-(Q3-S)") (class "Default")
      (node (ref "Color_sensor3") (pin "1") (pinfunction "1_1") (pintype "bidirectional"))
      (node (ref "Q3") (pin "2") (pinfunction "S_2") (pintype "passive"))
      (node (ref "Q6") (pin "1") (pinfunction "S_1") (pintype "passive"))
    )
    (net (code "66") (name "Net-(S1-P27)") (class "Default")
      (node (ref "J1") (pin "1") (pinfunction "1_1") (pintype "passive"))
      (node (ref "J4") (pin "1") (pinfunction "1_1") (pintype "passive"))
      (node (ref "S1") (pin "1") (pinfunction "P27_1") (pintype "passive"))
    )
    (net (code "67") (name "Net-(S2-P27)") (class "Default")
      (node (ref "J2") (pin "1") (pinfunction "1_1") (pintype "passive"))
      (node (ref "J5") (pin "1") (pinfunction "1_1") (pintype "passive"))
      (node (ref "S2") (pin "1") (pinfunction "P27_1") (pintype "passive"))
    )
    (net (code "68") (name "Net-(S3-P27)") (class "Default")
      (node (ref "J3") (pin "1") (pinfunction "1_1") (pintype "passive"))
      (node (ref "J6") (pin "1") (pinfunction "1_1") (pintype "passive"))
      (node (ref "S3") (pin "1") (pinfunction "P27_1") (pintype "passive"))
    )
    (net (code "69") (name "unconnected-(Arduino Mega-5V-Pad80)") (class "Default")
      (node (ref "Arduino Mega") (pin "80") (pinfunction "5V_80") (pintype "passive"))
    )
    (net (code "70") (name "unconnected-(Arduino Mega-5V-Pad81)") (class "Default")
      (node (ref "Arduino Mega") (pin "81") (pinfunction "5V_81") (pintype "passive"))
    )
    (net (code "71") (name "unconnected-(Arduino Mega-A0-Pad60)") (class "Default")
      (node (ref "Arduino Mega") (pin "60") (pinfunction "A0_60") (pintype "passive"))
    )
    (net (code "72") (name "unconnected-(Arduino Mega-A1-Pad61)") (class "Default")
      (node (ref "Arduino Mega") (pin "61") (pinfunction "A1_61") (pintype "passive"))
    )
    (net (code "73") (name "unconnected-(Arduino Mega-A2-Pad62)") (class "Default")
      (node (ref "Arduino Mega") (pin "62") (pinfunction "A2_62") (pintype "passive"))
    )
    (net (code "74") (name "unconnected-(Arduino Mega-A3-Pad63)") (class "Default")
      (node (ref "Arduino Mega") (pin "63") (pinfunction "A3_63") (pintype "passive"))
    )
    (net (code "75") (name "unconnected-(Arduino Mega-A4-Pad64)") (class "Default")
      (node (ref "Arduino Mega") (pin "64") (pinfunction "A4_64") (pintype "passive"))
    )
    (net (code "76") (name "unconnected-(Arduino Mega-A5-Pad65)") (class "Default")
      (node (ref "Arduino Mega") (pin "65") (pinfunction "A5_65") (pintype "passive"))
    )
    (net (code "77") (name "unconnected-(Arduino Mega-A6-Pad66)") (class "Default")
      (node (ref "Arduino Mega") (pin "66") (pinfunction "A6_66") (pintype "passive"))
    )
    (net (code "78") (name "unconnected-(Arduino Mega-A7-Pad67)") (class "Default")
      (node (ref "Arduino Mega") (pin "67") (pinfunction "A7_67") (pintype "passive"))
    )
    (net (code "79") (name "unconnected-(Arduino Mega-A8-Pad68)") (class "Default")
      (node (ref "Arduino Mega") (pin "68") (pinfunction "A8_68") (pintype "passive"))
    )
    (net (code "80") (name "unconnected-(Arduino Mega-A9-Pad69)") (class "Default")
      (node (ref "Arduino Mega") (pin "69") (pinfunction "A9_69") (pintype "passive"))
    )
    (net (code "81") (name "unconnected-(Arduino Mega-A10-Pad70)") (class "Default")
      (node (ref "Arduino Mega") (pin "70") (pinfunction "A10_70") (pintype "passive"))
    )
    (net (code "82") (name "unconnected-(Arduino Mega-A11-Pad71)") (class "Default")
      (node (ref "Arduino Mega") (pin "71") (pinfunction "A11_71") (pintype "passive"))
    )
    (net (code "83") (name "unconnected-(Arduino Mega-A12-Pad72)") (class "Default")
      (node (ref "Arduino Mega") (pin "72") (pinfunction "A12_72") (pintype "passive"))
    )
    (net (code "84") (name "unconnected-(Arduino Mega-A13-Pad73)") (class "Default")
      (node (ref "Arduino Mega") (pin "73") (pinfunction "A13_73") (pintype "passive"))
    )
    (net (code "85") (name "unconnected-(Arduino Mega-A14-Pad74)") (class "Default")
      (node (ref "Arduino Mega") (pin "74") (pinfunction "A14_74") (pintype "passive"))
    )
    (net (code "86") (name "unconnected-(Arduino Mega-A15-Pad75)") (class "Default")
      (node (ref "Arduino Mega") (pin "75") (pinfunction "A15_75") (pintype "passive"))
    )
    (net (code "87") (name "unconnected-(Arduino Mega-AREF-Pad77)") (class "Default")
      (node (ref "Arduino Mega") (pin "77") (pinfunction "AREF_77") (pintype "passive"))
    )
    (net (code "88") (name "unconnected-(Arduino Mega-GND-Pad76)") (class "Default")
      (node (ref "Arduino Mega") (pin "76") (pinfunction "GND_76") (pintype "passive"))
    )
    (net (code "89") (name "unconnected-(Arduino Mega-GND-Pad78)") (class "Default")
      (node (ref "Arduino Mega") (pin "78") (pinfunction "GND_78") (pintype "passive"))
    )
    (net (code "90") (name "unconnected-(Arduino Mega-GND-Pad79)") (class "Default")
      (node (ref "Arduino Mega") (pin "79") (pinfunction "GND_79") (pintype "passive"))
    )
    (net (code "91") (name "unconnected-(Arduino Mega-INT4{slash}RX1-Pad19)") (class "Default")
      (node (ref "Arduino Mega") (pin "19") (pinfunction "INT4/RX1_19") (pintype "passive"))
    )
    (net (code "92") (name "unconnected-(Arduino Mega-INT5{slash}TX1-Pad18)") (class "Default")
      (node (ref "Arduino Mega") (pin "18") (pinfunction "INT5/TX1_18") (pintype "passive"))
    )
    (net (code "93") (name "unconnected-(Arduino Mega-MOSI-Pad51)") (class "Default")
      (node (ref "Arduino Mega") (pin "51") (pinfunction "MOSI_51") (pintype "passive"))
    )
    (net (code "94") (name "unconnected-(Arduino Mega-RESET-Pad54)") (class "Default")
      (node (ref "Arduino Mega") (pin "54") (pinfunction "RESET_54") (pintype "passive"))
    )
    (net (code "95") (name "unconnected-(Arduino Mega-RX2-Pad17)") (class "Default")
      (node (ref "Arduino Mega") (pin "17") (pinfunction "RX2_17") (pintype "passive"))
    )
    (net (code "96") (name "unconnected-(Arduino Mega-RX3-Pad15)") (class "Default")
      (node (ref "Arduino Mega") (pin "15") (pinfunction "RX3_15") (pintype "passive"))
    )
    (net (code "97") (name "unconnected-(Arduino Mega-SCK-Pad52)") (class "Default")
      (node (ref "Arduino Mega") (pin "52") (pinfunction "SCK_52") (pintype "passive"))
    )
    (net (code "98") (name "unconnected-(Arduino Mega-SS-Pad53)") (class "Default")
      (node (ref "Arduino Mega") (pin "53") (pinfunction "SS_53") (pintype "passive"))
    )
    (net (code "99") (name "unconnected-(Arduino Mega-TX2-Pad16)") (class "Default")
      (node (ref "Arduino Mega") (pin "16") (pinfunction "TX2_16") (pintype "passive"))
    )
    (net (code "100") (name "unconnected-(Arduino Mega-TX3-Pad14)") (class "Default")
      (node (ref "Arduino Mega") (pin "14") (pinfunction "TX3_14") (pintype "passive"))
    )
    (net (code "101") (name "unconnected-(Arduino Mega-USB-RX0-Pad0)") (class "Default")
      (node (ref "Arduino Mega") (pin "0") (pinfunction "USB-RX0_0") (pintype "passive"))
    )
    (net (code "102") (name "unconnected-(Arduino Mega-USB-TX0-Pad1)") (class "Default")
      (node (ref "Arduino Mega") (pin "1") (pinfunction "USB-TX0_1") (pintype "passive"))
    )
    (net (code "103") (name "unconnected-(Color_sensor1-Pad5)") (class "Default")
      (node (ref "Color_sensor1") (pin "5") (pinfunction "5_5") (pintype "bidirectional"))
    )
    (net (code "104") (name "unconnected-(Color_sensor1-Pad6)") (class "Default")
      (node (ref "Color_sensor1") (pin "6") (pinfunction "6_6") (pintype "bidirectional"))
    )
    (net (code "105") (name "unconnected-(Color_sensor2-Pad5)") (class "Default")
      (node (ref "Color_sensor2") (pin "5") (pinfunction "5_5") (pintype "bidirectional"))
    )
    (net (code "106") (name "unconnected-(Color_sensor2-Pad6)") (class "Default")
      (node (ref "Color_sensor2") (pin "6") (pinfunction "6_6") (pintype "bidirectional"))
    )
    (net (code "107") (name "unconnected-(Color_sensor3-Pad5)") (class "Default")
      (node (ref "Color_sensor3") (pin "5") (pinfunction "5_5") (pintype "bidirectional"))
    )
    (net (code "108") (name "unconnected-(Color_sensor3-Pad6)") (class "Default")
      (node (ref "Color_sensor3") (pin "6") (pinfunction "6_6") (pintype "bidirectional"))
    )
    (net (code "109") (name "unconnected-(R13-Pad1)") (class "Default")
      (node (ref "R13") (pin "1") (pinfunction "1_1") (pintype "passive"))
    )
    (net (code "110") (name "unconnected-(R14-Pad2)") (class "Default")
      (node (ref "R14") (pin "2") (pinfunction "2_2") (pintype "passive"))
    )
    (net (code "111") (name "unconnected-(R15-Pad1)") (class "Default")
      (node (ref "R15") (pin "1") (pinfunction "1_1") (pintype "passive"))
    )
    (net (code "112") (name "unconnected-(R15-Pad2)") (class "Default")
      (node (ref "R15") (pin "2") (pinfunction "2_2") (pintype "passive"))
    )
    (net (code "113") (name "unconnected-(TOF_sensor1-Pad5)") (class "Default")
      (node (ref "TOF_sensor1") (pin "5") (pinfunction "5_5") (pintype "bidirectional"))
    )
    (net (code "114") (name "unconnected-(TOF_sensor2-Pad5)") (class "Default")
      (node (ref "TOF_sensor2") (pin "5") (pinfunction "5_5") (pintype "bidirectional"))
    )
    (net (code "115") (name "unconnected-(TOF_sensor3-Pad5)") (class "Default")
      (node (ref "TOF_sensor3") (pin "5") (pinfunction "5_5") (pintype "bidirectional"))
    )
    (net (code "116") (name "unconnected-(TOF_sensor4-Pad5)") (class "Default")
      (node (ref "TOF_sensor4") (pin "5") (pinfunction "5_5") (pintype "bidirectional"))
    )
    (net (code "117") (name "unconnected-(TOF_sensor5-Pad5)") (class "Default")
      (node (ref "TOF_sensor5") (pin "5") (pinfunction "5_5") (pintype "bidirectional"))
    )
    (net (code "118") (name "unconnected-(TOF_sensor6-Pad5)") (class "Default")
      (node (ref "TOF_sensor6") (pin "5") (pinfunction "5_5") (pintype "bidirectional"))
    )
    (net (code "119") (name "unconnected-(U1-1~{Q}-Pad14)") (class "Default")
      (node (ref "U1") (pin "14") (pinfunction "1~{Q}_14") (pintype "output"))
    )
    (net (code "120") (name "unconnected-(U1-2~{Q}-Pad10)") (class "Default")
      (node (ref "U1") (pin "10") (pinfunction "2~{Q}_10") (pintype "output"))
    )
    (net (code "121") (name "unconnected-(U2-1~{Q}-Pad14)") (class "Default")
      (node (ref "U2") (pin "14") (pinfunction "1~{Q}_14") (pintype "output"))
    )
    (net (code "122") (name "unconnected-(U2-2~{Q}-Pad10)") (class "Default")
      (node (ref "U2") (pin "10") (pinfunction "2~{Q}_10") (pintype "output"))
    )
    (net (code "123") (name "unconnected-(Uno1-Pad3V3)") (class "Default")
      (node (ref "Uno1") (pin "3V3") (pinfunction "3V3_3V3") (pintype "power_in"))
    )
    (net (code "124") (name "unconnected-(Uno1-PadA0)") (class "Default")
      (node (ref "Uno1") (pin "A0") (pinfunction "A0_A0") (pintype "bidirectional"))
    )
    (net (code "125") (name "unconnected-(Uno1-PadA1)") (class "Default")
      (node (ref "Uno1") (pin "A1") (pinfunction "A1_A1") (pintype "bidirectional"))
    )
    (net (code "126") (name "unconnected-(Uno1-PadA2)") (class "Default")
      (node (ref "Uno1") (pin "A2") (pinfunction "A2_A2") (pintype "bidirectional"))
    )
    (net (code "127") (name "unconnected-(Uno1-PadA3)") (class "Default")
      (node (ref "Uno1") (pin "A3") (pinfunction "A3_A3") (pintype "bidirectional"))
    )
    (net (code "128") (name "unconnected-(Uno1-PadA4)") (class "Default")
      (node (ref "Uno1") (pin "A4") (pinfunction "A4_A4") (pintype "bidirectional"))
    )
    (net (code "129") (name "unconnected-(Uno1-PadA5)") (class "Default")
      (node (ref "Uno1") (pin "A5") (pinfunction "A5_A5") (pintype "bidirectional"))
    )
    (net (code "130") (name "unconnected-(Uno1-PadAREF)") (class "Default")
      (node (ref "Uno1") (pin "AREF") (pinfunction "AREF_AREF") (pintype "bidirectional"))
    )
    (net (code "131") (name "unconnected-(Uno1-PadD0)") (class "Default")
      (node (ref "Uno1") (pin "D0") (pinfunction "D0_D0") (pintype "bidirectional"))
    )
    (net (code "132") (name "unconnected-(Uno1-PadD1)") (class "Default")
      (node (ref "Uno1") (pin "D1") (pinfunction "D1_D1") (pintype "bidirectional"))
    )
    (net (code "133") (name "unconnected-(Uno1-PadD4)") (class "Default")
      (node (ref "Uno1") (pin "D4") (pinfunction "D4_D4") (pintype "bidirectional"))
    )
    (net (code "134") (name "unconnected-(Uno1-PadD7)") (class "Default")
      (node (ref "Uno1") (pin "D7") (pinfunction "D7_D7") (pintype "bidirectional"))
    )
    (net (code "135") (name "unconnected-(Uno1-PadD9)") (class "Default")
      (node (ref "Uno1") (pin "D9") (pinfunction "D9_D9") (pintype "bidirectional"))
    )
    (net (code "136") (name "unconnected-(Uno1-PadD10)") (class "Default")
      (node (ref "Uno1") (pin "D10") (pinfunction "D10_D10") (pintype "bidirectional"))
    )
    (net (code "137") (name "unconnected-(Uno1-PadD11)") (class "Default")
      (node (ref "Uno1") (pin "D11") (pinfunction "D11_D11") (pintype "bidirectional"))
    )
    (net (code "138") (name "unconnected-(Uno1-PadD12)") (class "Default")
      (node (ref "Uno1") (pin "D12") (pinfunction "D12_D12") (pintype "bidirectional"))
    )
    (net (code "139") (name "unconnected-(Uno1-PadD13)") (class "Default")
      (node (ref "Uno1") (pin "D13") (pinfunction "D13_D13") (pintype "bidirectional"))
    )
    (net (code "140") (name "unconnected-(Uno1-PadIOREF)") (class "Default")
      (node (ref "Uno1") (pin "IOREF") (pinfunction "IOREF_IOREF") (pintype "bidirectional"))
    )
    (net (code "141") (name "unconnected-(Uno1-PadP1)") (class "Default")
      (node (ref "Uno1") (pin "P1") (pinfunction "P1_P1") (pintype "bidirectional"))
    )
    (net (code "142") (name "unconnected-(Uno1-PadRST)") (class "Default")
      (node (ref "Uno1") (pin "RST") (pinfunction "RST_RST") (pintype "bidirectional"))
    )
    (net (code "143") (name "unconnected-(Uno1D-AD4_SDA-PadA4_SDA)") (class "Default")
      (node (ref "Uno1") (pin "A4_SDA") (pinfunction "AD4_SDA_A4_SDA") (pintype "bidirectional"))
    )
    (net (code "144") (name "unconnected-(Uno1D-AD5_SCL-PadA5_SCL)") (class "Default")
      (node (ref "Uno1") (pin "A5_SCL") (pinfunction "AD5_SCL_A5_SCL") (pintype "bidirectional"))
    )
  )
)
